# fpga.net
KiCad netlist of a schematic drawn in Altium Designer
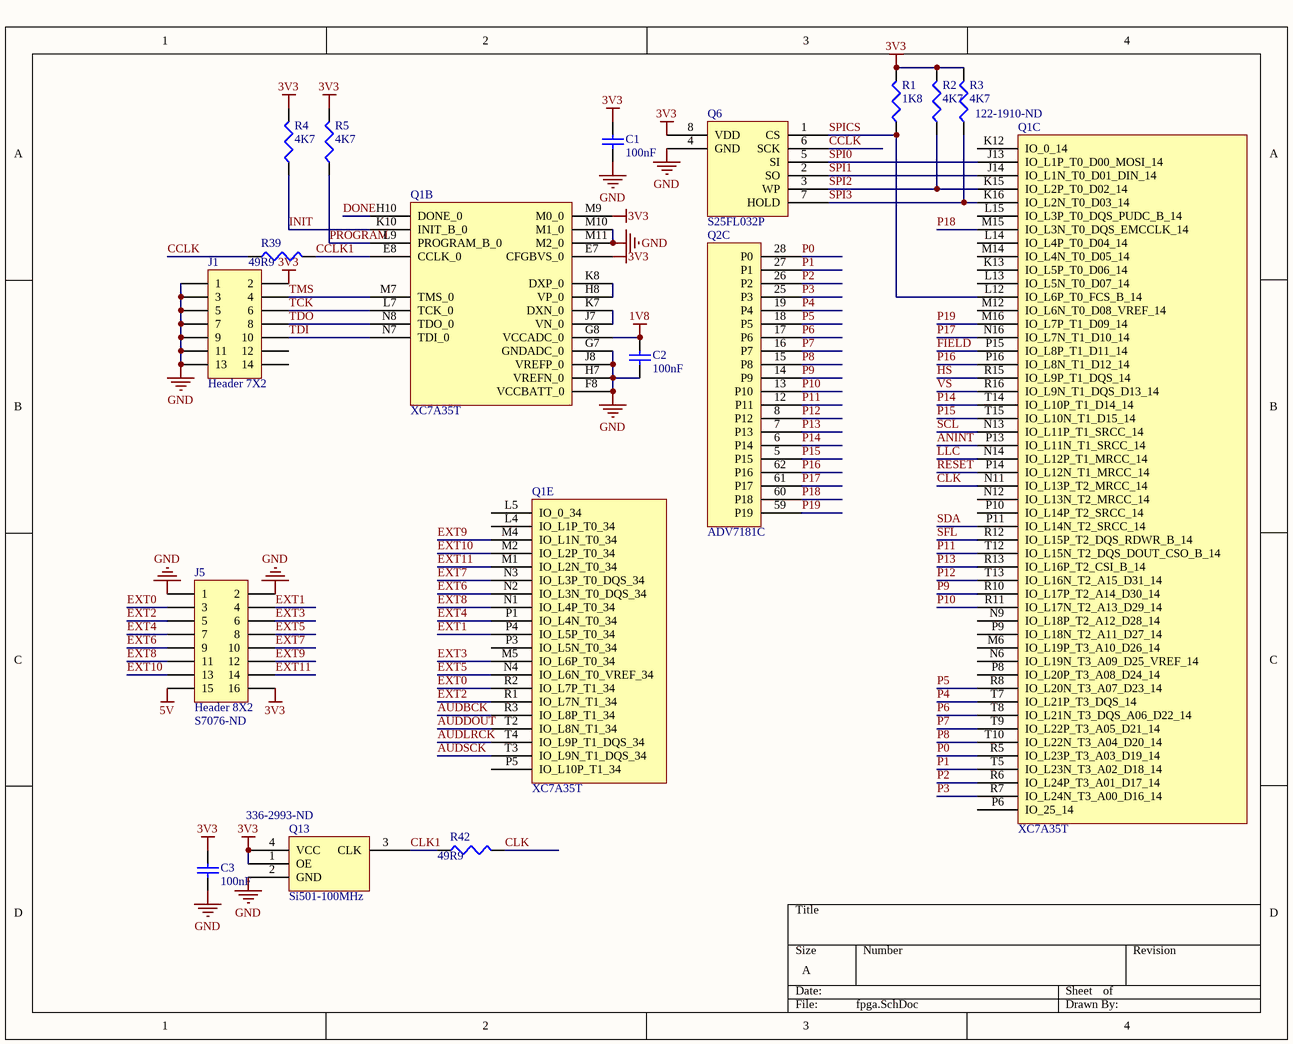
[diagram p0: fpga.SchDoc]

(export (version "E")
  (design (tool "Eeschema 10.0.6"))
  (components
    (comp (ref "C1")
      (value "100nF")
      (footprint "CAPC1005X06L")
      (description "Capacitor")
      (fields (field (name "Comment") "Cap") (field (name "PUBLISHER") "Altium Limited"))
      (libsource (lib "Miscellaneous Devices") (part "Cap"))
    )
    (comp (ref "C2")
      (value "100nF")
      (footprint "CAPC1005X06L")
      (description "Capacitor")
      (fields (field (name "Comment") "Cap") (field (name "PUBLISHER") "Altium Limited"))
      (libsource (lib "Miscellaneous Devices") (part "Cap"))
    )
    (comp (ref "C3")
      (value "100nF")
      (footprint "CAPC1005X06L")
      (description "Capacitor")
      (fields (field (name "Comment") "Cap") (field (name "PUBLISHER") "Altium Limited"))
      (libsource (lib "Miscellaneous Devices") (part "Cap"))
    )
    (comp (ref "J1")
      (value "Header 7X2")
      (footprint "HDR2X7")
      (description "Header, 7-Pin, Dual row")
      (fields (field (name "PUBLISHER") "Altium Limited"))
      (libsource (lib "Miscellaneous Connectors") (part "Header 7X2"))
    )
    (comp (ref "J5")
      (value "Header 8X2")
      (footprint "HDR2X8")
      (description "Header, 8-Pin, Dual row")
      (fields (field (name "SUPPLIER PART NUMBER 1") "S7076-ND") (field (name "PUBLISHER") "Altium Limited"))
      (libsource (lib "Miscellaneous Connectors") (part "Header 8X2"))
    )
    (comp (ref "Q1")
      (value "XC7A35T")
      (footprint "BGA256C100P16X16_1700X1700X155")
      (fields (field (name "SUPPLIER PART NUMBER 1") "122-1910-ND"))
      (libsource (lib "schlib") (part "XC7A35T"))
    )
    (comp (ref "Q2")
      (value "ADV7181C")
      (footprint "TSQFP50P1200X1200X145-64N")
      (libsource (lib "schlib") (part "ADV7181C"))
    )
    (comp (ref "Q6")
      (value "S25FL032P")
      (footprint "SOIC127P600X175-8AN")
      (libsource (lib "schlib") (part "S25FL032P"))
    )
    (comp (ref "Q13")
      (value "Si501-100MHz")
      (footprint "Si501_225")
      (fields (field (name "SUPPLIER PART NUMBER 1") "336-2993-ND"))
      (libsource (lib "schlib") (part "Si501"))
    )
    (comp (ref "R1")
      (value "1K8")
      (footprint "CAPC1608X90N")
      (description "Resistor")
      (fields (field (name "Comment") "Res3") (field (name "PUBLISHER") "Altium Limited"))
      (libsource (lib "Miscellaneous Devices") (part "Res3"))
    )
    (comp (ref "R2")
      (value "4K7")
      (footprint "CAPC1608X90N")
      (description "Resistor")
      (fields (field (name "Comment") "Res3") (field (name "PUBLISHER") "Altium Limited"))
      (libsource (lib "Miscellaneous Devices") (part "Res3"))
    )
    (comp (ref "R3")
      (value "4K7")
      (footprint "CAPC1608X90N")
      (description "Resistor")
      (fields (field (name "Comment") "Res3") (field (name "PUBLISHER") "Altium Limited"))
      (libsource (lib "Miscellaneous Devices") (part "Res3"))
    )
    (comp (ref "R4")
      (value "4K7")
      (footprint "CAPC1608X90N")
      (description "Resistor")
      (fields (field (name "Comment") "Res3") (field (name "PUBLISHER") "Altium Limited"))
      (libsource (lib "Miscellaneous Devices") (part "Res3"))
    )
    (comp (ref "R5")
      (value "4K7")
      (footprint "CAPC1608X90N")
      (description "Resistor")
      (fields (field (name "Comment") "Res3") (field (name "PUBLISHER") "Altium Limited"))
      (libsource (lib "Miscellaneous Devices") (part "Res3"))
    )
    (comp (ref "R39")
      (value "49R9")
      (footprint "CAPC1005X06L")
      (description "Resistor")
      (fields (field (name "Comment") "Res3") (field (name "PUBLISHER") "Altium Limited"))
      (libsource (lib "Miscellaneous Devices") (part "Res3"))
    )
    (comp (ref "R42")
      (value "49R9")
      (footprint "CAPC1005X06L")
      (description "Resistor")
      (fields (field (name "Comment") "Res3") (field (name "PUBLISHER") "Altium Limited"))
      (libsource (lib "Miscellaneous Devices") (part "Res3"))
    )
  )
  (nets
    (net (code "1") (name "/ANINT") (class "Default")
      (node (ref "Q1") (pin "P13") (pinfunction "IO_L11N_T1_SRCC_14_P13") (pintype "passive"))
    )
    (net (code "2") (name "/AUDBCK") (class "Default")
      (node (ref "Q1") (pin "R3") (pinfunction "IO_L8P_T1_34_R3") (pintype "passive"))
    )
    (net (code "3") (name "/AUDDOUT") (class "Default")
      (node (ref "Q1") (pin "T2") (pinfunction "IO_L8N_T1_34_T2") (pintype "passive"))
    )
    (net (code "4") (name "/AUDLRCK") (class "Default")
      (node (ref "Q1") (pin "T4") (pinfunction "IO_L9P_T1_DQS_34_T4") (pintype "passive"))
    )
    (net (code "5") (name "/AUDSCK") (class "Default")
      (node (ref "Q1") (pin "T3") (pinfunction "IO_L9N_T1_DQS_34_T3") (pintype "passive"))
    )
    (net (code "6") (name "/CCLK") (class "Default")
      (node (ref "Q6") (pin "6") (pinfunction "SCK_6") (pintype "passive"))
      (node (ref "R39") (pin "1") (pinfunction "1_1") (pintype "passive"))
    )
    (net (code "7") (name "/CCLK1") (class "Default")
      (node (ref "Q1") (pin "E8") (pinfunction "CCLK_0_E8") (pintype "passive"))
      (node (ref "R39") (pin "2") (pinfunction "2_2") (pintype "passive"))
    )
    (net (code "8") (name "/CLK") (class "Default")
      (node (ref "Q1") (pin "N11") (pinfunction "IO_L13P_T2_MRCC_14_N11") (pintype "passive"))
      (node (ref "R42") (pin "2") (pinfunction "2_2") (pintype "passive"))
    )
    (net (code "9") (name "/CLK1") (class "Default")
      (node (ref "Q13") (pin "3") (pinfunction "CLK_3") (pintype "passive"))
      (node (ref "R42") (pin "1") (pinfunction "1_1") (pintype "passive"))
    )
    (net (code "10") (name "/DONE") (class "Default")
      (node (ref "Q1") (pin "H10") (pinfunction "DONE_0_H10") (pintype "passive"))
    )
    (net (code "11") (name "/EXT0") (class "Default")
      (node (ref "J5") (pin "3") (pinfunction "3_3") (pintype "passive"))
      (node (ref "Q1") (pin "R2") (pinfunction "IO_L7P_T1_34_R2") (pintype "passive"))
    )
    (net (code "12") (name "/EXT1") (class "Default")
      (node (ref "J5") (pin "4") (pinfunction "4_4") (pintype "passive"))
      (node (ref "Q1") (pin "P4") (pinfunction "IO_L5P_T0_34_P4") (pintype "passive"))
    )
    (net (code "13") (name "/EXT2") (class "Default")
      (node (ref "J5") (pin "5") (pinfunction "5_5") (pintype "passive"))
      (node (ref "Q1") (pin "R1") (pinfunction "IO_L7N_T1_34_R1") (pintype "passive"))
    )
    (net (code "14") (name "/EXT3") (class "Default")
      (node (ref "J5") (pin "6") (pinfunction "6_6") (pintype "passive"))
      (node (ref "Q1") (pin "M5") (pinfunction "IO_L6P_T0_34_M5") (pintype "passive"))
    )
    (net (code "15") (name "/EXT4") (class "Default")
      (node (ref "J5") (pin "7") (pinfunction "7_7") (pintype "passive"))
      (node (ref "Q1") (pin "P1") (pinfunction "IO_L4N_T0_34_P1") (pintype "passive"))
    )
    (net (code "16") (name "/EXT5") (class "Default")
      (node (ref "J5") (pin "8") (pinfunction "8_8") (pintype "passive"))
      (node (ref "Q1") (pin "N4") (pinfunction "IO_L6N_T0_VREF_34_N4") (pintype "passive"))
    )
    (net (code "17") (name "/EXT6") (class "Default")
      (node (ref "J5") (pin "9") (pinfunction "9_9") (pintype "passive"))
      (node (ref "Q1") (pin "N2") (pinfunction "IO_L3N_T0_DQS_34_N2") (pintype "passive"))
    )
    (net (code "18") (name "/EXT7") (class "Default")
      (node (ref "J5") (pin "10") (pinfunction "10_10") (pintype "passive"))
      (node (ref "Q1") (pin "N3") (pinfunction "IO_L3P_T0_DQS_34_N3") (pintype "passive"))
    )
    (net (code "19") (name "/EXT8") (class "Default")
      (node (ref "J5") (pin "11") (pinfunction "11_11") (pintype "passive"))
      (node (ref "Q1") (pin "N1") (pinfunction "IO_L4P_T0_34_N1") (pintype "passive"))
    )
    (net (code "20") (name "/EXT9") (class "Default")
      (node (ref "J5") (pin "12") (pinfunction "12_12") (pintype "passive"))
      (node (ref "Q1") (pin "M4") (pinfunction "IO_L1N_T0_34_M4") (pintype "passive"))
    )
    (net (code "21") (name "/EXT10") (class "Default")
      (node (ref "J5") (pin "13") (pinfunction "13_13") (pintype "passive"))
      (node (ref "Q1") (pin "M2") (pinfunction "IO_L2P_T0_34_M2") (pintype "passive"))
    )
    (net (code "22") (name "/EXT11") (class "Default")
      (node (ref "J5") (pin "14") (pinfunction "14_14") (pintype "passive"))
      (node (ref "Q1") (pin "M1") (pinfunction "IO_L2N_T0_34_M1") (pintype "passive"))
    )
    (net (code "23") (name "/FIELD") (class "Default")
      (node (ref "Q1") (pin "P15") (pinfunction "IO_L8P_T1_D11_14_P15") (pintype "passive"))
    )
    (net (code "24") (name "/HS") (class "Default")
      (node (ref "Q1") (pin "R15") (pinfunction "IO_L9P_T1_DQS_14_R15") (pintype "passive"))
    )
    (net (code "25") (name "/INIT") (class "Default")
      (node (ref "Q1") (pin "K10") (pinfunction "INIT_B_0_K10") (pintype "passive"))
      (node (ref "R4") (pin "1") (pinfunction "1_1") (pintype "passive"))
    )
    (net (code "26") (name "/LLC") (class "Default")
      (node (ref "Q1") (pin "N14") (pinfunction "IO_L12P_T1_MRCC_14_N14") (pintype "passive"))
    )
    (net (code "27") (name "/P0") (class "Default")
      (node (ref "Q1") (pin "R5") (pinfunction "IO_L23P_T3_A03_D19_14_R5") (pintype "passive"))
      (node (ref "Q2") (pin "28") (pinfunction "P0_28") (pintype "passive"))
    )
    (net (code "28") (name "/P1") (class "Default")
      (node (ref "Q1") (pin "T5") (pinfunction "IO_L23N_T3_A02_D18_14_T5") (pintype "passive"))
      (node (ref "Q2") (pin "27") (pinfunction "P1_27") (pintype "passive"))
    )
    (net (code "29") (name "/P2") (class "Default")
      (node (ref "Q1") (pin "R6") (pinfunction "IO_L24P_T3_A01_D17_14_R6") (pintype "passive"))
      (node (ref "Q2") (pin "26") (pinfunction "P2_26") (pintype "passive"))
    )
    (net (code "30") (name "/P3") (class "Default")
      (node (ref "Q1") (pin "R7") (pinfunction "IO_L24N_T3_A00_D16_14_R7") (pintype "passive"))
      (node (ref "Q2") (pin "25") (pinfunction "P3_25") (pintype "passive"))
    )
    (net (code "31") (name "/P4") (class "Default")
      (node (ref "Q1") (pin "T7") (pinfunction "IO_L21P_T3_DQS_14_T7") (pintype "passive"))
      (node (ref "Q2") (pin "19") (pinfunction "P4_19") (pintype "passive"))
    )
    (net (code "32") (name "/P5") (class "Default")
      (node (ref "Q1") (pin "R8") (pinfunction "IO_L20N_T3_A07_D23_14_R8") (pintype "passive"))
      (node (ref "Q2") (pin "18") (pinfunction "P5_18") (pintype "passive"))
    )
    (net (code "33") (name "/P6") (class "Default")
      (node (ref "Q1") (pin "T8") (pinfunction "IO_L21N_T3_DQS_A06_D22_14_T8") (pintype "passive"))
      (node (ref "Q2") (pin "17") (pinfunction "P6_17") (pintype "passive"))
    )
    (net (code "34") (name "/P7") (class "Default")
      (node (ref "Q1") (pin "T9") (pinfunction "IO_L22P_T3_A05_D21_14_T9") (pintype "passive"))
      (node (ref "Q2") (pin "16") (pinfunction "P7_16") (pintype "passive"))
    )
    (net (code "35") (name "/P8") (class "Default")
      (node (ref "Q1") (pin "T10") (pinfunction "IO_L22N_T3_A04_D20_14_T10") (pintype "passive"))
      (node (ref "Q2") (pin "15") (pinfunction "P8_15") (pintype "passive"))
    )
    (net (code "36") (name "/P9") (class "Default")
      (node (ref "Q1") (pin "R10") (pinfunction "IO_L17P_T2_A14_D30_14_R10") (pintype "passive"))
      (node (ref "Q2") (pin "14") (pinfunction "P9_14") (pintype "passive"))
    )
    (net (code "37") (name "/P10") (class "Default")
      (node (ref "Q1") (pin "R11") (pinfunction "IO_L17N_T2_A13_D29_14_R11") (pintype "passive"))
      (node (ref "Q2") (pin "13") (pinfunction "P10_13") (pintype "passive"))
    )
    (net (code "38") (name "/P11") (class "Default")
      (node (ref "Q1") (pin "T12") (pinfunction "IO_L15N_T2_DQS_DOUT_CSO_B_14_T12") (pintype "passive"))
      (node (ref "Q2") (pin "12") (pinfunction "P11_12") (pintype "passive"))
    )
    (net (code "39") (name "/P12") (class "Default")
      (node (ref "Q1") (pin "T13") (pinfunction "IO_L16N_T2_A15_D31_14_T13") (pintype "passive"))
      (node (ref "Q2") (pin "8") (pinfunction "P12_8") (pintype "passive"))
    )
    (net (code "40") (name "/P13") (class "Default")
      (node (ref "Q1") (pin "R13") (pinfunction "IO_L16P_T2_CSI_B_14_R13") (pintype "passive"))
      (node (ref "Q2") (pin "7") (pinfunction "P13_7") (pintype "passive"))
    )
    (net (code "41") (name "/P14") (class "Default")
      (node (ref "Q1") (pin "T14") (pinfunction "IO_L10P_T1_D14_14_T14") (pintype "passive"))
      (node (ref "Q2") (pin "6") (pinfunction "P14_6") (pintype "passive"))
    )
    (net (code "42") (name "/P15") (class "Default")
      (node (ref "Q1") (pin "T15") (pinfunction "IO_L10N_T1_D15_14_T15") (pintype "passive"))
      (node (ref "Q2") (pin "5") (pinfunction "P15_5") (pintype "passive"))
    )
    (net (code "43") (name "/P16") (class "Default")
      (node (ref "Q1") (pin "P16") (pinfunction "IO_L8N_T1_D12_14_P16") (pintype "passive"))
      (node (ref "Q2") (pin "62") (pinfunction "P16_62") (pintype "passive"))
    )
    (net (code "44") (name "/P17") (class "Default")
      (node (ref "Q1") (pin "N16") (pinfunction "IO_L7N_T1_D10_14_N16") (pintype "passive"))
      (node (ref "Q2") (pin "61") (pinfunction "P17_61") (pintype "passive"))
    )
    (net (code "45") (name "/P18") (class "Default")
      (node (ref "Q1") (pin "M15") (pinfunction "IO_L3N_T0_DQS_EMCCLK_14_M15") (pintype "passive"))
      (node (ref "Q2") (pin "60") (pinfunction "P18_60") (pintype "passive"))
    )
    (net (code "46") (name "/P19") (class "Default")
      (node (ref "Q1") (pin "M16") (pinfunction "IO_L7P_T1_D09_14_M16") (pintype "passive"))
      (node (ref "Q2") (pin "59") (pinfunction "P19_59") (pintype "passive"))
    )
    (net (code "47") (name "/PROGRAM") (class "Default")
      (node (ref "Q1") (pin "L9") (pinfunction "PROGRAM_B_0_L9") (pintype "passive"))
      (node (ref "R5") (pin "1") (pinfunction "1_1") (pintype "passive"))
    )
    (net (code "48") (name "/RESET") (class "Default")
      (node (ref "Q1") (pin "P14") (pinfunction "IO_L12N_T1_MRCC_14_P14") (pintype "passive"))
    )
    (net (code "49") (name "/SCL") (class "Default")
      (node (ref "Q1") (pin "N13") (pinfunction "IO_L11P_T1_SRCC_14_N13") (pintype "passive"))
    )
    (net (code "50") (name "/SDA") (class "Default")
      (node (ref "Q1") (pin "P11") (pinfunction "IO_L14N_T2_SRCC_14_P11") (pintype "passive"))
    )
    (net (code "51") (name "/SFL") (class "Default")
      (node (ref "Q1") (pin "R12") (pinfunction "IO_L15P_T2_DQS_RDWR_B_14_R12") (pintype "passive"))
    )
    (net (code "52") (name "/SPI0") (class "Default")
      (node (ref "Q1") (pin "J13") (pinfunction "IO_L1P_T0_D00_MOSI_14_J13") (pintype "passive"))
      (node (ref "Q6") (pin "5") (pinfunction "SI_5") (pintype "passive"))
    )
    (net (code "53") (name "/SPI1") (class "Default")
      (node (ref "Q1") (pin "J14") (pinfunction "IO_L1N_T0_D01_DIN_14_J14") (pintype "passive"))
      (node (ref "Q6") (pin "2") (pinfunction "SO_2") (pintype "passive"))
    )
    (net (code "54") (name "/SPI2") (class "Default")
      (node (ref "Q1") (pin "K15") (pinfunction "IO_L2P_T0_D02_14_K15") (pintype "passive"))
      (node (ref "Q6") (pin "3") (pinfunction "WP_3") (pintype "passive"))
      (node (ref "R2") (pin "1") (pinfunction "1_1") (pintype "passive"))
    )
    (net (code "55") (name "/SPI3") (class "Default")
      (node (ref "Q1") (pin "K16") (pinfunction "IO_L2N_T0_D03_14_K16") (pintype "passive"))
      (node (ref "Q6") (pin "7") (pinfunction "HOLD_7") (pintype "passive"))
      (node (ref "R3") (pin "1") (pinfunction "1_1") (pintype "passive"))
    )
    (net (code "56") (name "/SPICS") (class "Default")
      (node (ref "Q1") (pin "L12") (pinfunction "IO_L6P_T0_FCS_B_14_L12") (pintype "passive"))
      (node (ref "Q6") (pin "1") (pinfunction "CS_1") (pintype "passive"))
      (node (ref "R1") (pin "1") (pinfunction "1_1") (pintype "passive"))
    )
    (net (code "57") (name "/TCK") (class "Default")
      (node (ref "J1") (pin "6") (pinfunction "6_6") (pintype "passive"))
      (node (ref "Q1") (pin "L7") (pinfunction "TCK_0_L7") (pintype "passive"))
    )
    (net (code "58") (name "/TDI") (class "Default")
      (node (ref "J1") (pin "10") (pinfunction "10_10") (pintype "passive"))
      (node (ref "Q1") (pin "N7") (pinfunction "TDI_0_N7") (pintype "passive"))
    )
    (net (code "59") (name "/TDO") (class "Default")
      (node (ref "J1") (pin "8") (pinfunction "8_8") (pintype "passive"))
      (node (ref "Q1") (pin "N8") (pinfunction "TDO_0_N8") (pintype "passive"))
    )
    (net (code "60") (name "/TMS") (class "Default")
      (node (ref "J1") (pin "4") (pinfunction "4_4") (pintype "passive"))
      (node (ref "Q1") (pin "M7") (pinfunction "TMS_0_M7") (pintype "passive"))
    )
    (net (code "61") (name "/VS") (class "Default")
      (node (ref "Q1") (pin "R16") (pinfunction "IO_L9N_T1_DQS_D13_14_R16") (pintype "passive"))
    )
    (net (code "62") (name "1V8") (class "Default")
      (node (ref "C2") (pin "2") (pinfunction "2_2") (pintype "passive"))
      (node (ref "Q1") (pin "G8") (pinfunction "VCCADC_0_G8") (pintype "passive"))
    )
    (net (code "63") (name "3V3") (class "Default")
      (node (ref "C1") (pin "2") (pinfunction "2_2") (pintype "passive"))
      (node (ref "C3") (pin "2") (pinfunction "2_2") (pintype "passive"))
      (node (ref "J1") (pin "2") (pinfunction "2_2") (pintype "passive"))
      (node (ref "J5") (pin "16") (pinfunction "16_16") (pintype "passive"))
      (node (ref "Q1") (pin "E7") (pinfunction "CFGBVS_0_E7") (pintype "passive"))
      (node (ref "Q1") (pin "M9") (pinfunction "M0_0_M9") (pintype "passive"))
      (node (ref "Q13") (pin "1") (pinfunction "OE_1") (pintype "passive"))
      (node (ref "Q13") (pin "4") (pinfunction "VCC_4") (pintype "passive"))
      (node (ref "Q6") (pin "8") (pinfunction "VDD_8") (pintype "passive"))
      (node (ref "R1") (pin "2") (pinfunction "2_2") (pintype "passive"))
      (node (ref "R2") (pin "2") (pinfunction "2_2") (pintype "passive"))
      (node (ref "R3") (pin "2") (pinfunction "2_2") (pintype "passive"))
      (node (ref "R4") (pin "2") (pinfunction "2_2") (pintype "passive"))
      (node (ref "R5") (pin "2") (pinfunction "2_2") (pintype "passive"))
    )
    (net (code "64") (name "5V") (class "Default")
      (node (ref "J5") (pin "15") (pinfunction "15_15") (pintype "passive"))
    )
    (net (code "65") (name "GND") (class "Default")
      (node (ref "C1") (pin "1") (pinfunction "1_1") (pintype "passive"))
      (node (ref "C2") (pin "1") (pinfunction "1_1") (pintype "passive"))
      (node (ref "C3") (pin "1") (pinfunction "1_1") (pintype "passive"))
      (node (ref "J1") (pin "1") (pinfunction "1_1") (pintype "passive"))
      (node (ref "J1") (pin "11") (pinfunction "11_11") (pintype "passive"))
      (node (ref "J1") (pin "13") (pinfunction "13_13") (pintype "passive"))
      (node (ref "J1") (pin "3") (pinfunction "3_3") (pintype "passive"))
      (node (ref "J1") (pin "5") (pinfunction "5_5") (pintype "passive"))
      (node (ref "J1") (pin "7") (pinfunction "7_7") (pintype "passive"))
      (node (ref "J1") (pin "9") (pinfunction "9_9") (pintype "passive"))
      (node (ref "J5") (pin "1") (pinfunction "1_1") (pintype "passive"))
      (node (ref "J5") (pin "2") (pinfunction "2_2") (pintype "passive"))
      (node (ref "Q1") (pin "F8") (pinfunction "VCCBATT_0_F8") (pintype "passive"))
      (node (ref "Q1") (pin "G7") (pinfunction "GNDADC_0_G7") (pintype "passive"))
      (node (ref "Q1") (pin "H7") (pinfunction "VREFN_0_H7") (pintype "passive"))
      (node (ref "Q1") (pin "J8") (pinfunction "VREFP_0_J8") (pintype "passive"))
      (node (ref "Q1") (pin "M10") (pinfunction "M1_0_M10") (pintype "passive"))
      (node (ref "Q1") (pin "M11") (pinfunction "M2_0_M11") (pintype "passive"))
      (node (ref "Q13") (pin "2") (pinfunction "GND_2") (pintype "passive"))
      (node (ref "Q6") (pin "4") (pinfunction "GND_4") (pintype "passive"))
    )
    (net (code "66") (name "Net-(Q1B-DXN_0)") (class "Default")
      (node (ref "Q1") (pin "J7") (pinfunction "VN_0_J7") (pintype "passive"))
      (node (ref "Q1") (pin "K7") (pinfunction "DXN_0_K7") (pintype "passive"))
    )
    (net (code "67") (name "Net-(Q1B-DXP_0)") (class "Default")
      (node (ref "Q1") (pin "H8") (pinfunction "VP_0_H8") (pintype "passive"))
      (node (ref "Q1") (pin "K8") (pinfunction "DXP_0_K8") (pintype "passive"))
    )
    (net (code "68") (name "unconnected-(J1-Pad12)") (class "Default")
      (node (ref "J1") (pin "12") (pinfunction "12_12") (pintype "passive"))
    )
    (net (code "69") (name "unconnected-(J1-Pad14)") (class "Default")
      (node (ref "J1") (pin "14") (pinfunction "14_14") (pintype "passive"))
    )
    (net (code "70") (name "unconnected-(Q1C-IO_0_14-PadK12)") (class "Default")
      (node (ref "Q1") (pin "K12") (pinfunction "IO_0_14_K12") (pintype "passive"))
    )
    (net (code "71") (name "unconnected-(Q1C-IO_25_14-PadP6)") (class "Default")
      (node (ref "Q1") (pin "P6") (pinfunction "IO_25_14_P6") (pintype "passive"))
    )
    (net (code "72") (name "unconnected-(Q1C-IO_L3P_T0_DQS_PUDC_B_14-PadL15)") (class "Default")
      (node (ref "Q1") (pin "L15") (pinfunction "IO_L3P_T0_DQS_PUDC_B_14_L15") (pintype "passive"))
    )
    (net (code "73") (name "unconnected-(Q1C-IO_L4N_T0_D05_14-PadM14)") (class "Default")
      (node (ref "Q1") (pin "M14") (pinfunction "IO_L4N_T0_D05_14_M14") (pintype "passive"))
    )
    (net (code "74") (name "unconnected-(Q1C-IO_L4P_T0_D04_14-PadL14)") (class "Default")
      (node (ref "Q1") (pin "L14") (pinfunction "IO_L4P_T0_D04_14_L14") (pintype "passive"))
    )
    (net (code "75") (name "unconnected-(Q1C-IO_L5N_T0_D07_14-PadL13)") (class "Default")
      (node (ref "Q1") (pin "L13") (pinfunction "IO_L5N_T0_D07_14_L13") (pintype "passive"))
    )
    (net (code "76") (name "unconnected-(Q1C-IO_L5P_T0_D06_14-PadK13)") (class "Default")
      (node (ref "Q1") (pin "K13") (pinfunction "IO_L5P_T0_D06_14_K13") (pintype "passive"))
    )
    (net (code "77") (name "unconnected-(Q1C-IO_L6N_T0_D08_VREF_14-PadM12)") (class "Default")
      (node (ref "Q1") (pin "M12") (pinfunction "IO_L6N_T0_D08_VREF_14_M12") (pintype "passive"))
    )
    (net (code "78") (name "unconnected-(Q1C-IO_L13N_T2_MRCC_14-PadN12)") (class "Default")
      (node (ref "Q1") (pin "N12") (pinfunction "IO_L13N_T2_MRCC_14_N12") (pintype "passive"))
    )
    (net (code "79") (name "unconnected-(Q1C-IO_L14P_T2_SRCC_14-PadP10)") (class "Default")
      (node (ref "Q1") (pin "P10") (pinfunction "IO_L14P_T2_SRCC_14_P10") (pintype "passive"))
    )
    (net (code "80") (name "unconnected-(Q1C-IO_L18N_T2_A11_D27_14-PadP9)") (class "Default")
      (node (ref "Q1") (pin "P9") (pinfunction "IO_L18N_T2_A11_D27_14_P9") (pintype "passive"))
    )
    (net (code "81") (name "unconnected-(Q1C-IO_L18P_T2_A12_D28_14-PadN9)") (class "Default")
      (node (ref "Q1") (pin "N9") (pinfunction "IO_L18P_T2_A12_D28_14_N9") (pintype "passive"))
    )
    (net (code "82") (name "unconnected-(Q1C-IO_L19N_T3_A09_D25_VREF_14-PadN6)") (class "Default")
      (node (ref "Q1") (pin "N6") (pinfunction "IO_L19N_T3_A09_D25_VREF_14_N6") (pintype "passive"))
    )
    (net (code "83") (name "unconnected-(Q1C-IO_L19P_T3_A10_D26_14-PadM6)") (class "Default")
      (node (ref "Q1") (pin "M6") (pinfunction "IO_L19P_T3_A10_D26_14_M6") (pintype "passive"))
    )
    (net (code "84") (name "unconnected-(Q1C-IO_L20P_T3_A08_D24_14-PadP8)") (class "Default")
      (node (ref "Q1") (pin "P8") (pinfunction "IO_L20P_T3_A08_D24_14_P8") (pintype "passive"))
    )
    (net (code "85") (name "unconnected-(Q1E-IO_0_34-PadL5)") (class "Default")
      (node (ref "Q1") (pin "L5") (pinfunction "IO_0_34_L5") (pintype "passive"))
    )
    (net (code "86") (name "unconnected-(Q1E-IO_L1P_T0_34-PadL4)") (class "Default")
      (node (ref "Q1") (pin "L4") (pinfunction "IO_L1P_T0_34_L4") (pintype "passive"))
    )
    (net (code "87") (name "unconnected-(Q1E-IO_L5N_T0_34-PadP3)") (class "Default")
      (node (ref "Q1") (pin "P3") (pinfunction "IO_L5N_T0_34_P3") (pintype "passive"))
    )
    (net (code "88") (name "unconnected-(Q1E-IO_L10P_T1_34-PadP5)") (class "Default")
      (node (ref "Q1") (pin "P5") (pinfunction "IO_L10P_T1_34_P5") (pintype "passive"))
    )
  )
)
